# 6-Safety-Relay-Schematic.net
KiCad netlist of a schematic drawn in Altium Designer
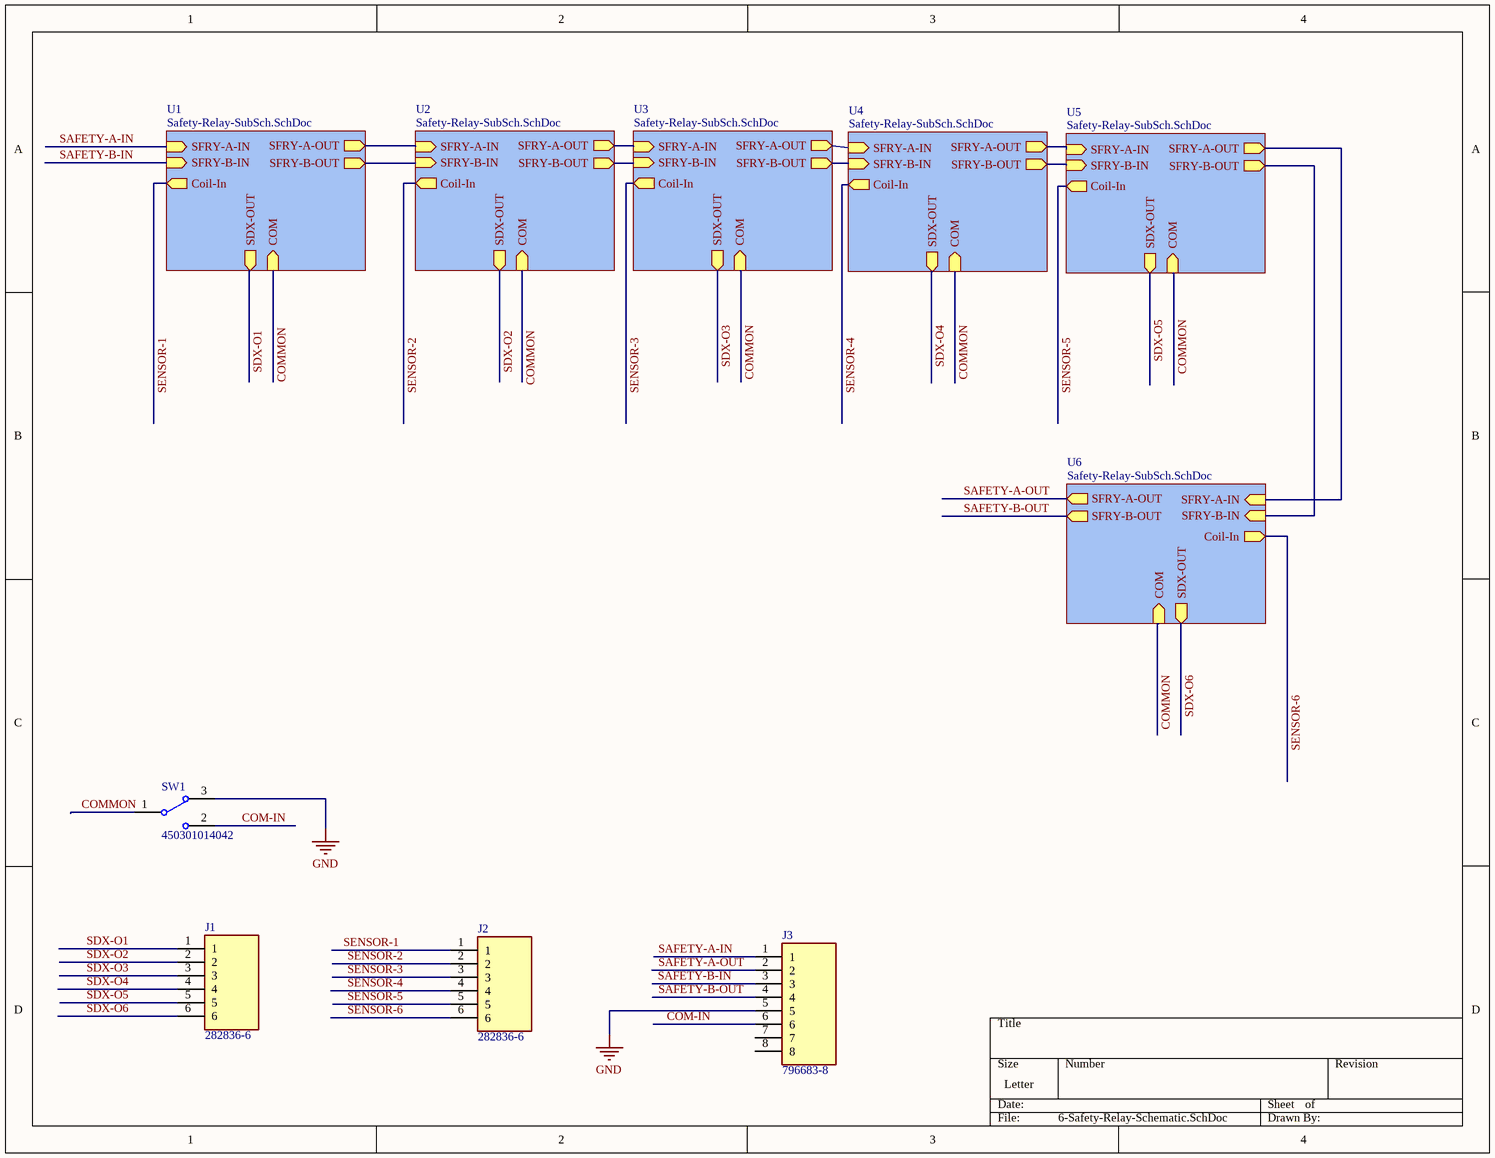
[diagram p0: 6-Safety-Relay-Schematic.SchDoc]

(export (version "E")
  (design (tool "Eeschema 10.0.6"))
  (components
    (comp (ref "J1")
      (value "282836-6")
      (footprint "SamacSys:SHDR6W100P0X500_1X6_3000X820X1000P")
      (description "Connector")
      (fields (field (name "MOUSER PART NUMBER") "571-2828366") (field (name "RS PART NUMBER") "3617702"))
      (libsource (lib "*") (part "282836-6"))
    )
    (comp (ref "J2")
      (value "282836-6")
      (footprint "SamacSys:SHDR6W100P0X500_1X6_3000X820X1000P")
      (description "Connector")
      (fields (field (name "MOUSER PART NUMBER") "571-2828366") (field (name "RS PART NUMBER") "3617702"))
      (libsource (lib "*") (part "282836-6"))
    )
    (comp (ref "J3")
      (value "796683-8")
      (footprint "SamacSys:SHDR8W110P0X500_1X8_4000X900X1520P")
      (description "Connector")
      (fields (field (name "MOUSER PART NUMBER") "571-796683-8"))
      (libsource (lib "*") (part "796683-8"))
    )
    (comp (ref "SW1")
      (value "450301014042")
      (footprint "450301014042")
      (description "WS-SLTV 10mm*2.5mm, SPDT, ON-ON, 2.54mm, straight type, THT, Mini Slide Switch, 3 pins")
      (fields (field (name "MANUFACTURER") "Wuerth Elektronik"))
      (libsource (lib "Altium Content Vault") (part "WE-SLIDE-SW-3"))
    )
  )
  (nets
    (net (code "1") (name "/COM-IN") (class "Default")
      (node (ref "J3") (pin "6") (pinfunction "6_6") (pintype "passive"))
      (node (ref "SW1") (pin "2") (pinfunction "2_2") (pintype "passive"))
    )
    (net (code "2") (name "/COMMON") (class "Default")
      (node (ref "SW1") (pin "1") (pinfunction "1_1") (pintype "passive"))
    )
    (net (code "3") (name "/SAFETY-A-IN") (class "Default")
      (node (ref "J3") (pin "1") (pinfunction "1_1") (pintype "passive"))
    )
    (net (code "4") (name "/SAFETY-A-OUT") (class "Default")
      (node (ref "J3") (pin "2") (pinfunction "2_2") (pintype "passive"))
    )
    (net (code "5") (name "/SAFETY-B-IN") (class "Default")
      (node (ref "J3") (pin "3") (pinfunction "3_3") (pintype "passive"))
    )
    (net (code "6") (name "/SAFETY-B-OUT") (class "Default")
      (node (ref "J3") (pin "4") (pinfunction "4_4") (pintype "passive"))
    )
    (net (code "7") (name "/SDX-O1") (class "Default")
      (node (ref "J1") (pin "1") (pinfunction "1_1") (pintype "passive"))
    )
    (net (code "8") (name "/SDX-O2") (class "Default")
      (node (ref "J1") (pin "2") (pinfunction "2_2") (pintype "passive"))
    )
    (net (code "9") (name "/SDX-O3") (class "Default")
      (node (ref "J1") (pin "3") (pinfunction "3_3") (pintype "passive"))
    )
    (net (code "10") (name "/SDX-O4") (class "Default")
      (node (ref "J1") (pin "4") (pinfunction "4_4") (pintype "passive"))
    )
    (net (code "11") (name "/SDX-O5") (class "Default")
      (node (ref "J1") (pin "5") (pinfunction "5_5") (pintype "passive"))
    )
    (net (code "12") (name "/SDX-O6") (class "Default")
      (node (ref "J1") (pin "6") (pinfunction "6_6") (pintype "passive"))
    )
    (net (code "13") (name "/SENSOR-1") (class "Default")
      (node (ref "J2") (pin "1") (pinfunction "1_1") (pintype "passive"))
    )
    (net (code "14") (name "/SENSOR-2") (class "Default")
      (node (ref "J2") (pin "2") (pinfunction "2_2") (pintype "passive"))
    )
    (net (code "15") (name "/SENSOR-3") (class "Default")
      (node (ref "J2") (pin "3") (pinfunction "3_3") (pintype "passive"))
    )
    (net (code "16") (name "/SENSOR-4") (class "Default")
      (node (ref "J2") (pin "4") (pinfunction "4_4") (pintype "passive"))
    )
    (net (code "17") (name "/SENSOR-5") (class "Default")
      (node (ref "J2") (pin "5") (pinfunction "5_5") (pintype "passive"))
    )
    (net (code "18") (name "/SENSOR-6") (class "Default")
      (node (ref "J2") (pin "6") (pinfunction "6_6") (pintype "passive"))
    )
    (net (code "29") (name "GND") (class "Default")
      (node (ref "J3") (pin "5") (pinfunction "5_5") (pintype "passive"))
      (node (ref "SW1") (pin "3") (pinfunction "3_3") (pintype "passive"))
    )
    (net (code "30") (name "unconnected-(J3-Pad7)") (class "Default")
      (node (ref "J3") (pin "7") (pinfunction "7_7") (pintype "passive"))
    )
    (net (code "31") (name "unconnected-(J3-Pad8)") (class "Default")
      (node (ref "J3") (pin "8") (pinfunction "8_8") (pintype "passive"))
    )
  )
)
